# Stepper_Motor_Driver_v1_0.net
KiCad netlist of a schematic drawn in EAGLE
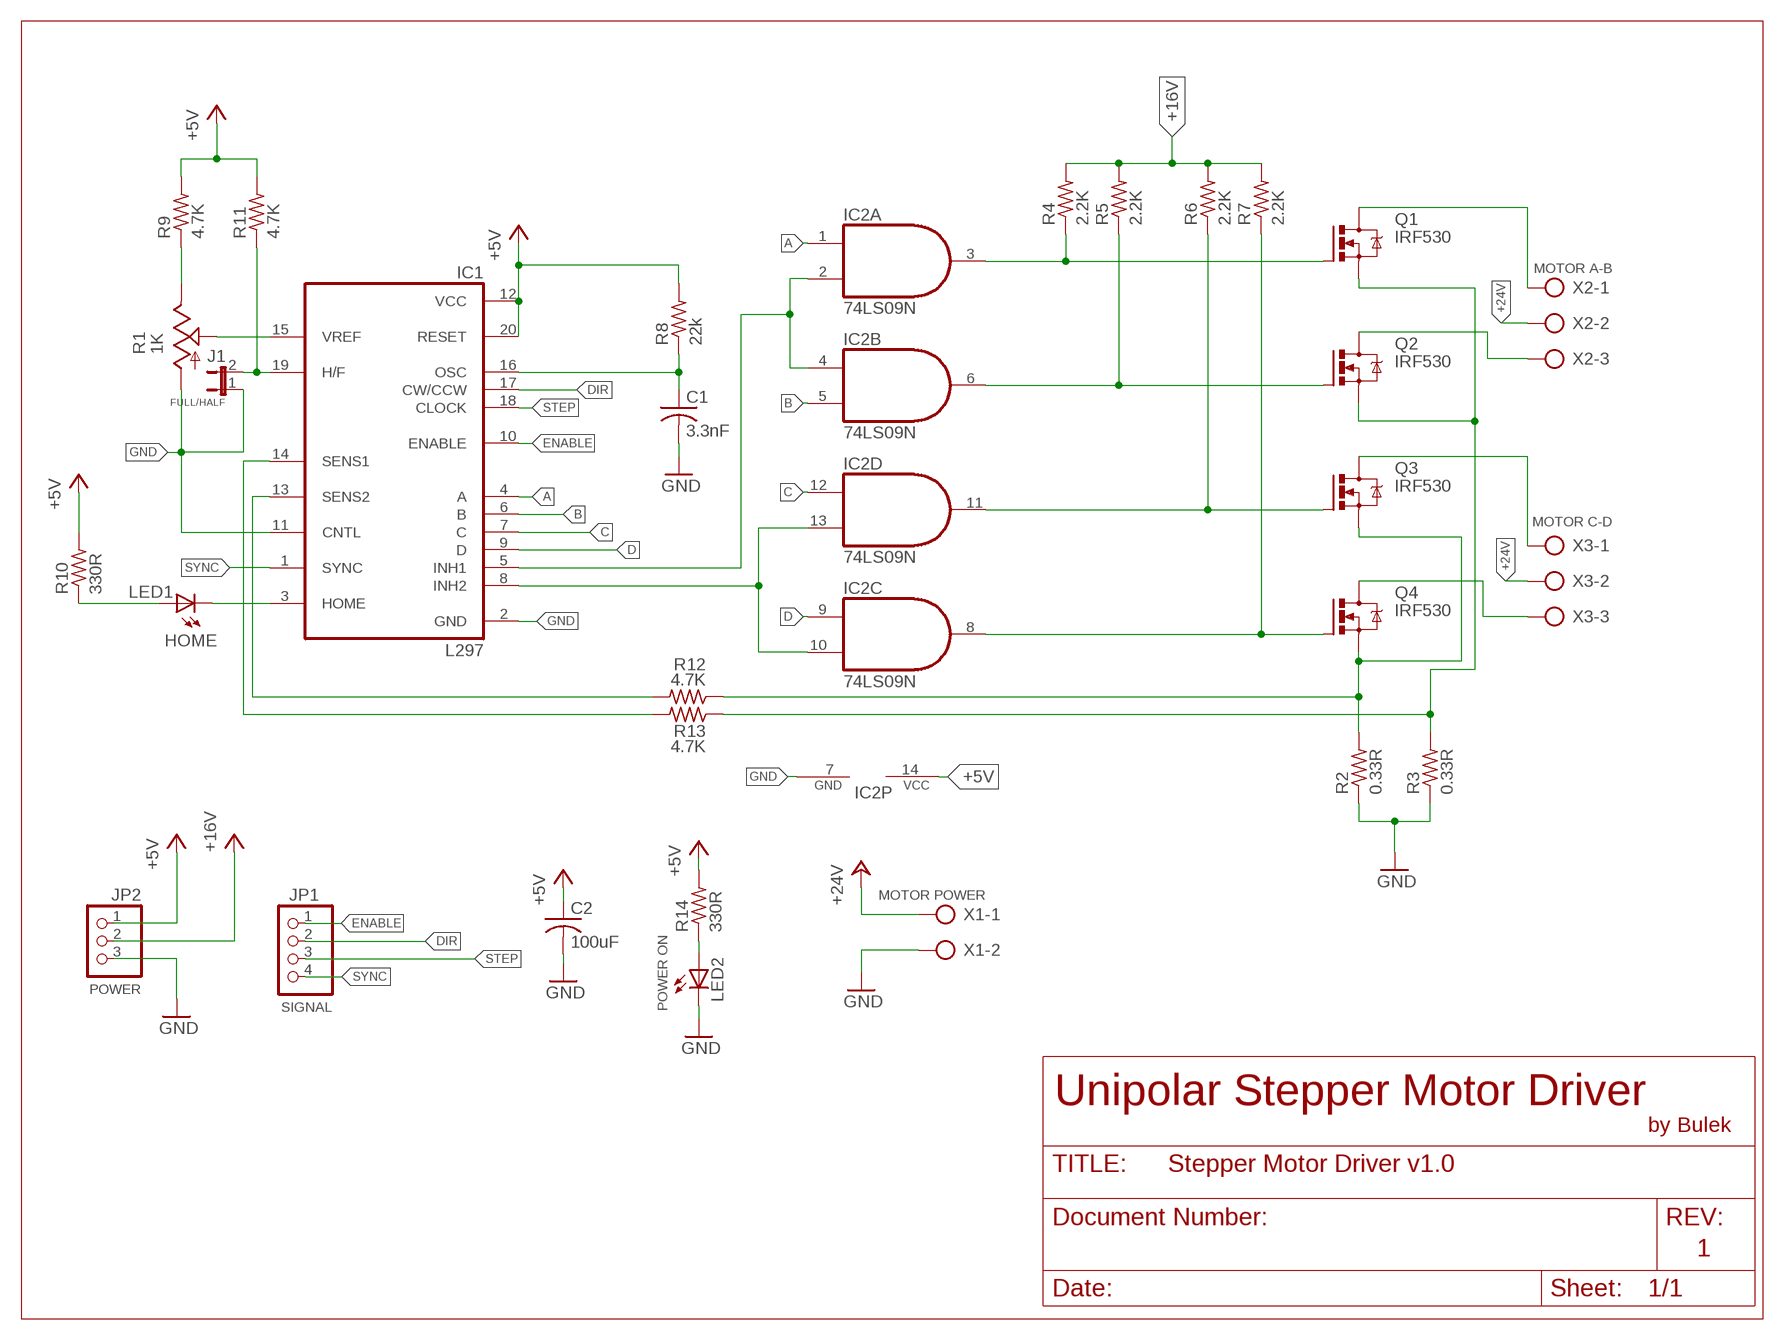
[diagram p0: schematic, sheet 1]

(export (version "E")
  (design (tool "Eeschema 10.0.6"))
  (components
    (comp (ref "C1")
      (value "3.3nF")
      (footprint "eagle-import:C025-024X044")
      (libsource (lib "eagle-import") (part "C-US025-024X044"))
    )
    (comp (ref "C2")
      (value "100uF")
      (footprint "eagle-import:C025-024X044")
      (libsource (lib "eagle-import") (part "C-US025-024X044"))
    )
    (comp (ref "FULL/HALF")
      (value "J1")
      (footprint "eagle-import:JP1")
      (libsource (lib "eagle-import") (part "JP1E"))
    )
    (comp (ref "IC1")
      (value "L297")
      (footprint "eagle-import:DIL20")
      (fields (field (name "MPN") "L297/1"))
      (libsource (lib "eagle-import") (part "L297"))
    )
    (comp (ref "IC2")
      (value "74LS09N")
      (footprint "eagle-import:DIL14")
      (libsource (lib "eagle-import") (part "7409NLS"))
    )
    (comp (ref "JP1")
      (value "SIGNAL")
      (footprint "eagle-import:1X04")
      (libsource (lib "eagle-import") (part "PINHD-1X4"))
    )
    (comp (ref "JP2")
      (value "POWER")
      (footprint "eagle-import:1X03_90")
      (libsource (lib "eagle-import") (part "PINHD-1X3/90"))
    )
    (comp (ref "LED1")
      (value "HOME")
      (footprint "eagle-import:LED5MM")
      (libsource (lib "eagle-import") (part "LED5MM"))
    )
    (comp (ref "LED2")
      (value "POWER ON")
      (footprint "eagle-import:LED5MM")
      (libsource (lib "eagle-import") (part "LED5MM"))
    )
    (comp (ref "Q1")
      (value "IRF530")
      (footprint "eagle-import:TO220BV")
      (libsource (lib "eagle-import") (part "IRF530"))
    )
    (comp (ref "Q2")
      (value "IRF530")
      (footprint "eagle-import:TO220BV")
      (libsource (lib "eagle-import") (part "IRF530"))
    )
    (comp (ref "Q3")
      (value "IRF530")
      (footprint "eagle-import:TO220BV")
      (libsource (lib "eagle-import") (part "IRF530"))
    )
    (comp (ref "Q4")
      (value "IRF530")
      (footprint "eagle-import:TO220BV")
      (libsource (lib "eagle-import") (part "IRF530"))
    )
    (comp (ref "R1")
      (value "1K")
      (footprint "eagle-import:S63X")
      (libsource (lib "eagle-import") (part "TRIM_US-S63X"))
    )
    (comp (ref "R2")
      (value "0.33R")
      (footprint "eagle-import:0617_22")
      (libsource (lib "eagle-import") (part "R-US_0617/22"))
    )
    (comp (ref "R3")
      (value "0.33R")
      (footprint "eagle-import:0617_22")
      (libsource (lib "eagle-import") (part "R-US_0617/22"))
    )
    (comp (ref "R4")
      (value "2.2K")
      (footprint "eagle-import:0207_10")
      (libsource (lib "eagle-import") (part "R-US_0207/10"))
    )
    (comp (ref "R5")
      (value "2.2K")
      (footprint "eagle-import:0207_10")
      (libsource (lib "eagle-import") (part "R-US_0207/10"))
    )
    (comp (ref "R6")
      (value "2.2K")
      (footprint "eagle-import:0207_10")
      (libsource (lib "eagle-import") (part "R-US_0207/10"))
    )
    (comp (ref "R7")
      (value "2.2K")
      (footprint "eagle-import:0207_10")
      (libsource (lib "eagle-import") (part "R-US_0207/10"))
    )
    (comp (ref "R8")
      (value "22k")
      (footprint "eagle-import:0207_10")
      (libsource (lib "eagle-import") (part "R-US_0207/10"))
    )
    (comp (ref "R9")
      (value "4.7K")
      (footprint "eagle-import:0207_10")
      (libsource (lib "eagle-import") (part "R-US_0207/10"))
    )
    (comp (ref "R10")
      (value "330R")
      (footprint "eagle-import:0207_10")
      (libsource (lib "eagle-import") (part "R-US_0207/10"))
    )
    (comp (ref "R11")
      (value "4.7K")
      (footprint "eagle-import:0207_10")
      (libsource (lib "eagle-import") (part "R-US_0207/10"))
    )
    (comp (ref "R12")
      (value "4.7K")
      (footprint "eagle-import:0207_10")
      (libsource (lib "eagle-import") (part "R-US_0207/10"))
    )
    (comp (ref "R13")
      (value "4.7K")
      (footprint "eagle-import:0207_10")
      (libsource (lib "eagle-import") (part "R-US_0207/10"))
    )
    (comp (ref "R14")
      (value "330R")
      (footprint "eagle-import:0207_10")
      (libsource (lib "eagle-import") (part "R-US_0207/10"))
    )
    (comp (ref "X1")
      (value "MOTOR POWER")
      (footprint "eagle-import:AK300_2")
      (libsource (lib "eagle-import") (part "AK300/2"))
    )
    (comp (ref "X2")
      (value "MOTOR A-B")
      (footprint "eagle-import:AK300_3")
      (libsource (lib "eagle-import") (part "AK300/3"))
    )
    (comp (ref "X3")
      (value "MOTOR C-D")
      (footprint "eagle-import:AK300_3")
      (libsource (lib "eagle-import") (part "AK300/3"))
    )
  )
  (nets
    (net (code "1") (name "+5V") (class "Default")
      (node (ref "C2") (pin "1") (pinfunction "1_1") (pintype "passive"))
      (node (ref "IC1") (pin "12") (pinfunction "VCC_12") (pintype "power_in"))
      (node (ref "IC1") (pin "20") (pinfunction "RESET_20") (pintype "input"))
      (node (ref "IC2") (pin "14") (pinfunction "VCC_14") (pintype "power_in"))
      (node (ref "JP2") (pin "1") (pinfunction "1_1") (pintype "passive"))
      (node (ref "R10") (pin "2") (pinfunction "2_2") (pintype "passive"))
      (node (ref "R11") (pin "2") (pinfunction "2_2") (pintype "passive"))
      (node (ref "R14") (pin "2") (pinfunction "2_2") (pintype "passive"))
      (node (ref "R8") (pin "2") (pinfunction "2_2") (pintype "passive"))
      (node (ref "R9") (pin "2") (pinfunction "2_2") (pintype "passive"))
    )
    (net (code "2") (name "+16V") (class "Default")
      (node (ref "JP2") (pin "2") (pinfunction "2_2") (pintype "passive"))
      (node (ref "R4") (pin "2") (pinfunction "2_2") (pintype "passive"))
      (node (ref "R5") (pin "2") (pinfunction "2_2") (pintype "passive"))
      (node (ref "R6") (pin "2") (pinfunction "2_2") (pintype "passive"))
      (node (ref "R7") (pin "2") (pinfunction "2_2") (pintype "passive"))
    )
    (net (code "3") (name "+24V") (class "Default")
      (node (ref "X1") (pin "1") (pinfunction "KL_1") (pintype "passive"))
      (node (ref "X2") (pin "2") (pinfunction "KL_2") (pintype "passive"))
      (node (ref "X3") (pin "2") (pinfunction "KL_2") (pintype "passive"))
    )
    (net (code "4") (name "A") (class "Default")
      (node (ref "IC1") (pin "4") (pinfunction "A_4") (pintype "output"))
      (node (ref "IC2") (pin "1") (pinfunction "I0_1") (pintype "input"))
    )
    (net (code "5") (name "B") (class "Default")
      (node (ref "IC1") (pin "6") (pinfunction "B_6") (pintype "output"))
      (node (ref "IC2") (pin "5") (pinfunction "I1_5") (pintype "input"))
    )
    (net (code "6") (name "C") (class "Default")
      (node (ref "IC1") (pin "7") (pinfunction "C_7") (pintype "output"))
      (node (ref "IC2") (pin "12") (pinfunction "I0_12") (pintype "input"))
    )
    (net (code "7") (name "D") (class "Default")
      (node (ref "IC1") (pin "9") (pinfunction "D_9") (pintype "output"))
      (node (ref "IC2") (pin "9") (pinfunction "I0_9") (pintype "input"))
    )
    (net (code "8") (name "DIR") (class "Default")
      (node (ref "IC1") (pin "17") (pinfunction "CW/CCW_17") (pintype "input"))
      (node (ref "JP1") (pin "2") (pinfunction "2_2") (pintype "passive"))
    )
    (net (code "9") (name "ENABLE") (class "Default")
      (node (ref "IC1") (pin "10") (pinfunction "ENABLE_10") (pintype "input"))
      (node (ref "JP1") (pin "1") (pinfunction "1_1") (pintype "passive"))
    )
    (net (code "10") (name "GND") (class "Default")
      (node (ref "C1") (pin "2") (pinfunction "2_2") (pintype "passive"))
      (node (ref "C2") (pin "2") (pinfunction "2_2") (pintype "passive"))
      (node (ref "FULL/HALF") (pin "1") (pinfunction "1_1") (pintype "passive"))
      (node (ref "IC1") (pin "11") (pinfunction "CNTL_11") (pintype "input"))
      (node (ref "IC1") (pin "2") (pinfunction "GND_2") (pintype "power_in"))
      (node (ref "IC2") (pin "7") (pinfunction "GND_7") (pintype "power_in"))
      (node (ref "JP2") (pin "3") (pinfunction "3_3") (pintype "passive"))
      (node (ref "LED2") (pin "K") (pinfunction "C_K") (pintype "passive"))
      (node (ref "R1") (pin "A") (pinfunction "A_A") (pintype "passive"))
      (node (ref "R2") (pin "1") (pinfunction "1_1") (pintype "passive"))
      (node (ref "R3") (pin "1") (pinfunction "1_1") (pintype "passive"))
      (node (ref "X1") (pin "2") (pinfunction "KL_2") (pintype "passive"))
    )
    (net (code "11") (name "Net-(IC1-HOME)") (class "Default")
      (node (ref "IC1") (pin "3") (pinfunction "HOME_3") (pintype "output"))
      (node (ref "LED1") (pin "K") (pinfunction "C_K") (pintype "passive"))
    )
    (net (code "12") (name "Net-(IC1-H{slash}F)") (class "Default")
      (node (ref "FULL/HALF") (pin "2") (pinfunction "2_2") (pintype "passive"))
      (node (ref "IC1") (pin "19") (pinfunction "H/F_19") (pintype "input"))
      (node (ref "R11") (pin "1") (pinfunction "1_1") (pintype "passive"))
    )
    (net (code "13") (name "Net-(IC1-INH1)") (class "Default")
      (node (ref "IC1") (pin "5") (pinfunction "INH1_5") (pintype "output"))
      (node (ref "IC2") (pin "2") (pinfunction "I1_2") (pintype "input"))
      (node (ref "IC2") (pin "4") (pinfunction "I0_4") (pintype "input"))
    )
    (net (code "14") (name "Net-(IC1-INH2)") (class "Default")
      (node (ref "IC1") (pin "8") (pinfunction "INH2_8") (pintype "output"))
      (node (ref "IC2") (pin "10") (pinfunction "I1_10") (pintype "input"))
      (node (ref "IC2") (pin "13") (pinfunction "I1_13") (pintype "input"))
    )
    (net (code "15") (name "Net-(IC1-OSC)") (class "Default")
      (node (ref "C1") (pin "1") (pinfunction "1_1") (pintype "passive"))
      (node (ref "IC1") (pin "16") (pinfunction "OSC_16") (pintype "bidirectional"))
      (node (ref "R8") (pin "1") (pinfunction "1_1") (pintype "passive"))
    )
    (net (code "16") (name "Net-(IC1-SENS1)") (class "Default")
      (node (ref "IC1") (pin "14") (pinfunction "SENS1_14") (pintype "output"))
      (node (ref "R13") (pin "2") (pinfunction "2_2") (pintype "passive"))
    )
    (net (code "17") (name "Net-(IC1-SENS2)") (class "Default")
      (node (ref "IC1") (pin "13") (pinfunction "SENS2_13") (pintype "output"))
      (node (ref "R12") (pin "2") (pinfunction "2_2") (pintype "passive"))
    )
    (net (code "18") (name "Net-(IC1-VREF)") (class "Default")
      (node (ref "IC1") (pin "15") (pinfunction "VREF_15") (pintype "input"))
      (node (ref "R1") (pin "S") (pinfunction "S_S") (pintype "passive"))
    )
    (net (code "19") (name "Net-(IC2A-O)") (class "Default")
      (node (ref "IC2") (pin "3") (pinfunction "O_3") (pintype "open_collector"))
      (node (ref "Q1") (pin "G") (pinfunction "G_G") (pintype "passive"))
      (node (ref "R4") (pin "1") (pinfunction "1_1") (pintype "passive"))
    )
    (net (code "20") (name "Net-(IC2B-O)") (class "Default")
      (node (ref "IC2") (pin "6") (pinfunction "O_6") (pintype "open_collector"))
      (node (ref "Q2") (pin "G") (pinfunction "G_G") (pintype "passive"))
      (node (ref "R5") (pin "1") (pinfunction "1_1") (pintype "passive"))
    )
    (net (code "21") (name "Net-(IC2C-O)") (class "Default")
      (node (ref "IC2") (pin "8") (pinfunction "O_8") (pintype "open_collector"))
      (node (ref "Q4") (pin "G") (pinfunction "G_G") (pintype "passive"))
      (node (ref "R7") (pin "1") (pinfunction "1_1") (pintype "passive"))
    )
    (net (code "22") (name "Net-(IC2D-O)") (class "Default")
      (node (ref "IC2") (pin "11") (pinfunction "O_11") (pintype "open_collector"))
      (node (ref "Q3") (pin "G") (pinfunction "G_G") (pintype "passive"))
      (node (ref "R6") (pin "1") (pinfunction "1_1") (pintype "passive"))
    )
    (net (code "23") (name "Net-(LED1-PadA)") (class "Default")
      (node (ref "LED1") (pin "A") (pinfunction "A_A") (pintype "passive"))
      (node (ref "R10") (pin "1") (pinfunction "1_1") (pintype "passive"))
    )
    (net (code "24") (name "Net-(LED2-PadA)") (class "Default")
      (node (ref "LED2") (pin "A") (pinfunction "A_A") (pintype "passive"))
      (node (ref "R14") (pin "1") (pinfunction "1_1") (pintype "passive"))
    )
    (net (code "25") (name "Net-(Q1-PadS)") (class "Default")
      (node (ref "Q1") (pin "S") (pinfunction "S_S") (pintype "passive"))
      (node (ref "Q2") (pin "S") (pinfunction "S_S") (pintype "passive"))
      (node (ref "R13") (pin "1") (pinfunction "1_1") (pintype "passive"))
      (node (ref "R3") (pin "2") (pinfunction "2_2") (pintype "passive"))
    )
    (net (code "26") (name "Net-(Q3-PadS)") (class "Default")
      (node (ref "Q3") (pin "S") (pinfunction "S_S") (pintype "passive"))
      (node (ref "Q4") (pin "S") (pinfunction "S_S") (pintype "passive"))
      (node (ref "R12") (pin "1") (pinfunction "1_1") (pintype "passive"))
      (node (ref "R2") (pin "2") (pinfunction "2_2") (pintype "passive"))
    )
    (net (code "27") (name "Net-(R1-PadE)") (class "Default")
      (node (ref "R1") (pin "E") (pinfunction "E_E") (pintype "passive"))
      (node (ref "R9") (pin "1") (pinfunction "1_1") (pintype "passive"))
    )
    (net (code "28") (name "Net-(X2A-KL)") (class "Default")
      (node (ref "Q1") (pin "D") (pinfunction "D_D") (pintype "passive"))
      (node (ref "X2") (pin "1") (pinfunction "KL_1") (pintype "passive"))
    )
    (net (code "29") (name "Net-(X2C-KL)") (class "Default")
      (node (ref "Q2") (pin "D") (pinfunction "D_D") (pintype "passive"))
      (node (ref "X2") (pin "3") (pinfunction "KL_3") (pintype "passive"))
    )
    (net (code "30") (name "Net-(X3A-KL)") (class "Default")
      (node (ref "Q3") (pin "D") (pinfunction "D_D") (pintype "passive"))
      (node (ref "X3") (pin "1") (pinfunction "KL_1") (pintype "passive"))
    )
    (net (code "31") (name "Net-(X3C-KL)") (class "Default")
      (node (ref "Q4") (pin "D") (pinfunction "D_D") (pintype "passive"))
      (node (ref "X3") (pin "3") (pinfunction "KL_3") (pintype "passive"))
    )
    (net (code "32") (name "STEP") (class "Default")
      (node (ref "IC1") (pin "18") (pinfunction "CLOCK_18") (pintype "input"))
      (node (ref "JP1") (pin "3") (pinfunction "3_3") (pintype "passive"))
    )
    (net (code "33") (name "SYNC") (class "Default")
      (node (ref "IC1") (pin "1") (pinfunction "SYNC_1") (pintype "output"))
    )
    (net (code "34") (name "unconnected-(JP1-Pad4)") (class "Default")
      (node (ref "JP1") (pin "4") (pinfunction "4_4") (pintype "passive"))
    )
  )
)
